# RoboBoard.net
KiCad netlist of a schematic drawn in EAGLE
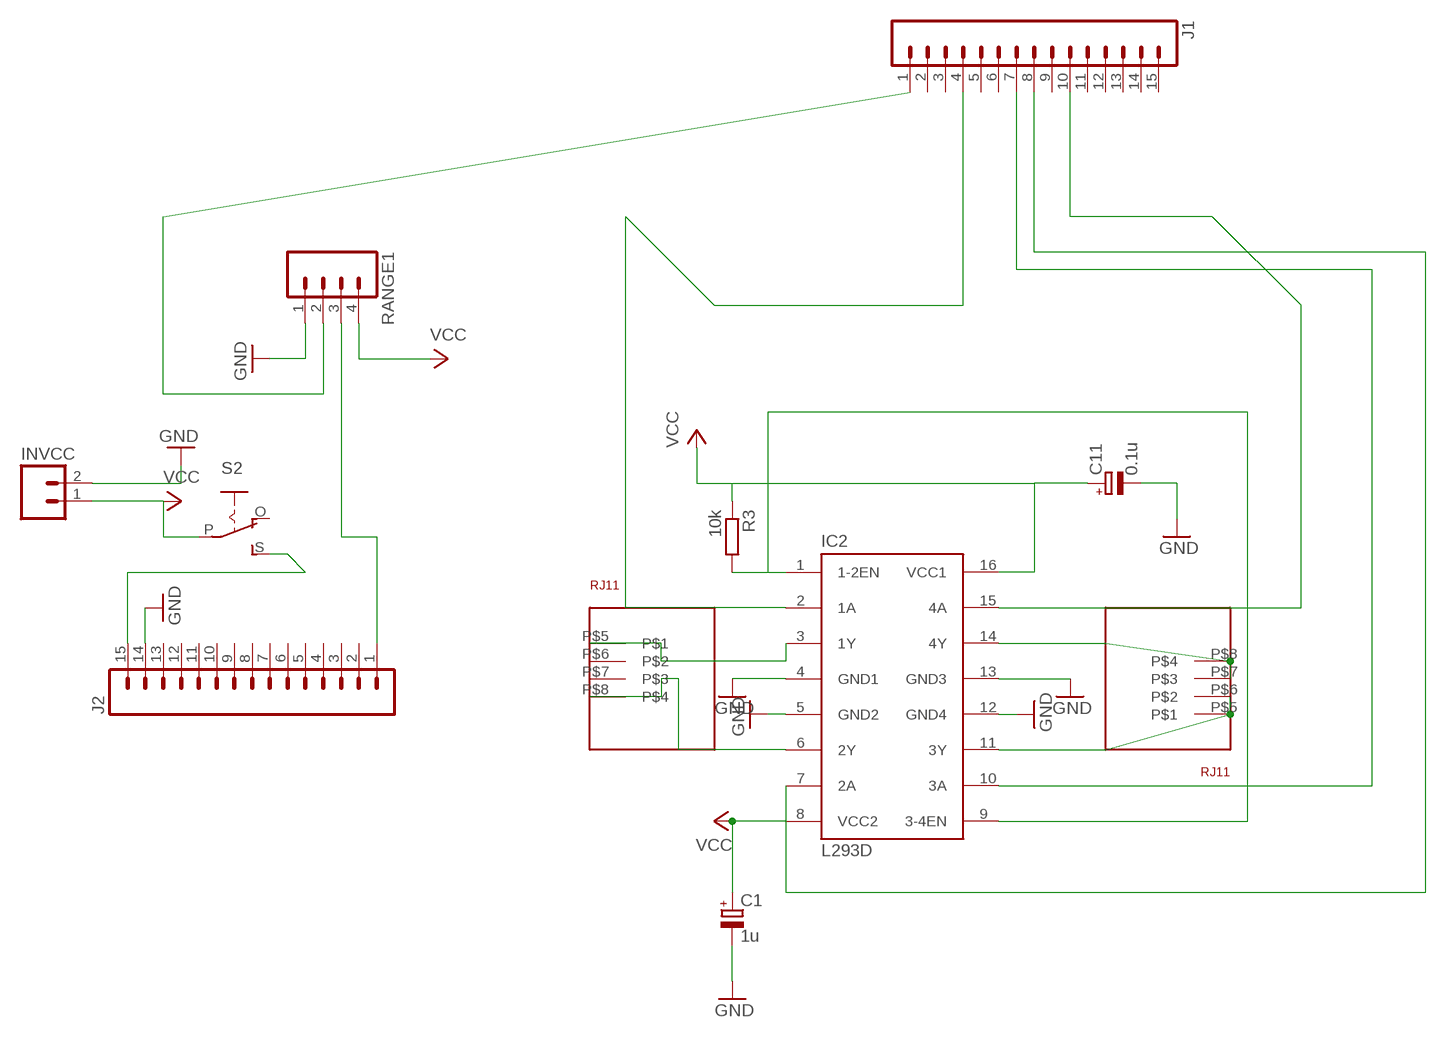
[diagram p0: schematic, sheet 1]

(export (version "E")
  (design (tool "Eeschema 10.0.6"))
  (components
    (comp (ref "C1")
      (value "1u")
      (footprint "eagle-import:E1,8-4")
      (libsource (lib "eagle-import") (part "CPOL-EUE1.8-4"))
    )
    (comp (ref "C11")
      (value "0.1u")
      (footprint "eagle-import:E1,8-4")
      (libsource (lib "eagle-import") (part "CPOL-EUE1.8-4"))
    )
    (comp (ref "IC2")
      (value "L293D")
      (footprint "eagle-import:DIL16")
      (libsource (lib "eagle-import") (part "L293D"))
    )
    (comp (ref "INVCC")
      (value "M02LOCK_LONGPADS")
      (footprint "eagle-import:1X02_LOCK_LONGPADS")
      (libsource (lib "eagle-import") (part "M02LOCK_LONGPADS"))
    )
    (comp (ref "J1")
      (value "M15LOCK_LONGPADS")
      (footprint "eagle-import:1X15_LOCK_LONGPADS")
      (libsource (lib "eagle-import") (part "M15LOCK_LONGPADS"))
    )
    (comp (ref "J2")
      (value "M15LOCK_LONGPADS")
      (footprint "eagle-import:1X15_LOCK_LONGPADS")
      (libsource (lib "eagle-import") (part "M15LOCK_LONGPADS"))
    )
    (comp (ref "R3")
      (value "10k")
      (footprint "eagle-import:0204_7")
      (libsource (lib "eagle-import") (part "R-EU_0204/7"))
    )
    (comp (ref "RANGE1")
      (value "M04LONGPADS")
      (footprint "eagle-import:1X04_LONGPADS")
      (libsource (lib "eagle-import") (part "M04LONGPADS"))
    )
    (comp (ref "RJ1")
      (value "RJ11")
      (footprint "eagle-import:RJ11-4PIN")
      (libsource (lib "eagle-import") (part "RJ11"))
    )
    (comp (ref "RJ2")
      (value "RJ11")
      (footprint "eagle-import:RJ11-4PIN")
      (libsource (lib "eagle-import") (part "RJ11"))
    )
    (comp (ref "S2")
      (value "EG1218S")
      (footprint "eagle-import:EG1218")
      (libsource (lib "eagle-import") (part "EG1218S"))
    )
  )
  (nets
    (net (code "1") (name "GND") (class "Default")
      (node (ref "C1") (pin "-") (pinfunction "-_-") (pintype "passive"))
      (node (ref "C11") (pin "-") (pinfunction "-_-") (pintype "passive"))
      (node (ref "IC2") (pin "12") (pinfunction "GND4_12") (pintype "power_in"))
      (node (ref "IC2") (pin "13") (pinfunction "GND3_13") (pintype "power_in"))
      (node (ref "IC2") (pin "4") (pinfunction "GND1_4") (pintype "power_in"))
      (node (ref "IC2") (pin "5") (pinfunction "GND2_5") (pintype "power_in"))
      (node (ref "INVCC") (pin "2") (pinfunction "2_2") (pintype "passive"))
      (node (ref "J2") (pin "14") (pinfunction "14_14") (pintype "passive"))
      (node (ref "RANGE1") (pin "1") (pinfunction "1_1") (pintype "passive"))
    )
    (net (code "2") (name "Net-(IC2-1-2EN)") (class "Default")
      (node (ref "IC2") (pin "1") (pinfunction "1-2EN_1") (pintype "input"))
      (node (ref "IC2") (pin "9") (pinfunction "3-4EN_9") (pintype "input"))
      (node (ref "R3") (pin "2") (pinfunction "2_2") (pintype "passive"))
    )
    (net (code "3") (name "Net-(IC2-1A)") (class "Default")
      (node (ref "IC2") (pin "2") (pinfunction "1A_2") (pintype "input"))
      (node (ref "J1") (pin "4") (pinfunction "4_4") (pintype "passive"))
    )
    (net (code "4") (name "Net-(IC2-1Y)") (class "Default")
      (node (ref "IC2") (pin "3") (pinfunction "1Y_3") (pintype "output"))
      (node (ref "RJ1") (pin "P$5") (pinfunction "P$1_P$5") (pintype "bidirectional"))
    )
    (net (code "5") (name "Net-(IC2-2A)") (class "Default")
      (node (ref "IC2") (pin "7") (pinfunction "2A_7") (pintype "input"))
      (node (ref "J1") (pin "8") (pinfunction "8_8") (pintype "passive"))
    )
    (net (code "6") (name "Net-(IC2-2Y)") (class "Default")
      (node (ref "IC2") (pin "6") (pinfunction "2Y_6") (pintype "output"))
      (node (ref "RJ1") (pin "P$8") (pinfunction "P$4_P$8") (pintype "bidirectional"))
    )
    (net (code "7") (name "Net-(IC2-3A)") (class "Default")
      (node (ref "IC2") (pin "10") (pinfunction "3A_10") (pintype "input"))
      (node (ref "J1") (pin "7") (pinfunction "7_7") (pintype "passive"))
    )
    (net (code "8") (name "Net-(IC2-3Y)") (class "Default")
      (node (ref "IC2") (pin "11") (pinfunction "3Y_11") (pintype "output"))
      (node (ref "RJ2") (pin "P$5") (pinfunction "P$1_P$5") (pintype "bidirectional"))
      (node (ref "RJ2") (pin "P$6") (pinfunction "P$2_P$6") (pintype "bidirectional"))
    )
    (net (code "9") (name "Net-(IC2-4A)") (class "Default")
      (node (ref "IC2") (pin "15") (pinfunction "4A_15") (pintype "input"))
      (node (ref "J1") (pin "10") (pinfunction "10_10") (pintype "passive"))
    )
    (net (code "10") (name "Net-(IC2-4Y)") (class "Default")
      (node (ref "IC2") (pin "14") (pinfunction "4Y_14") (pintype "output"))
      (node (ref "RJ2") (pin "P$7") (pinfunction "P$3_P$7") (pintype "bidirectional"))
      (node (ref "RJ2") (pin "P$8") (pinfunction "P$4_P$8") (pintype "bidirectional"))
    )
    (net (code "11") (name "Net-(J1-Pad1)") (class "Default")
      (node (ref "J1") (pin "1") (pinfunction "1_1") (pintype "passive"))
      (node (ref "RANGE1") (pin "2") (pinfunction "2_2") (pintype "passive"))
    )
    (net (code "12") (name "Net-(J2-Pad1)") (class "Default")
      (node (ref "J2") (pin "1") (pinfunction "1_1") (pintype "passive"))
      (node (ref "RANGE1") (pin "3") (pinfunction "3_3") (pintype "passive"))
    )
    (net (code "13") (name "Net-(J2-Pad15)") (class "Default")
      (node (ref "J2") (pin "15") (pinfunction "15_15") (pintype "passive"))
      (node (ref "S2") (pin "S") (pinfunction "S_S") (pintype "passive"))
    )
    (net (code "14") (name "VCC") (class "Default")
      (node (ref "C1") (pin "+") (pinfunction "+_+") (pintype "passive"))
      (node (ref "C11") (pin "+") (pinfunction "+_+") (pintype "passive"))
      (node (ref "IC2") (pin "16") (pinfunction "VCC1_16") (pintype "power_in"))
      (node (ref "IC2") (pin "8") (pinfunction "VCC2_8") (pintype "power_in"))
      (node (ref "INVCC") (pin "1") (pinfunction "1_1") (pintype "passive"))
      (node (ref "R3") (pin "1") (pinfunction "1_1") (pintype "passive"))
      (node (ref "RANGE1") (pin "4") (pinfunction "4_4") (pintype "passive"))
      (node (ref "S2") (pin "P") (pinfunction "P_P") (pintype "passive"))
    )
    (net (code "15") (name "unconnected-(J1-Pad2)") (class "Default")
      (node (ref "J1") (pin "2") (pinfunction "2_2") (pintype "passive"))
    )
    (net (code "16") (name "unconnected-(J1-Pad3)") (class "Default")
      (node (ref "J1") (pin "3") (pinfunction "3_3") (pintype "passive"))
    )
    (net (code "17") (name "unconnected-(J1-Pad5)") (class "Default")
      (node (ref "J1") (pin "5") (pinfunction "5_5") (pintype "passive"))
    )
    (net (code "18") (name "unconnected-(J1-Pad6)") (class "Default")
      (node (ref "J1") (pin "6") (pinfunction "6_6") (pintype "passive"))
    )
    (net (code "19") (name "unconnected-(J1-Pad9)") (class "Default")
      (node (ref "J1") (pin "9") (pinfunction "9_9") (pintype "passive"))
    )
    (net (code "20") (name "unconnected-(J1-Pad11)") (class "Default")
      (node (ref "J1") (pin "11") (pinfunction "11_11") (pintype "passive"))
    )
    (net (code "21") (name "unconnected-(J1-Pad12)") (class "Default")
      (node (ref "J1") (pin "12") (pinfunction "12_12") (pintype "passive"))
    )
    (net (code "22") (name "unconnected-(J1-Pad13)") (class "Default")
      (node (ref "J1") (pin "13") (pinfunction "13_13") (pintype "passive"))
    )
    (net (code "23") (name "unconnected-(J1-Pad14)") (class "Default")
      (node (ref "J1") (pin "14") (pinfunction "14_14") (pintype "passive"))
    )
    (net (code "24") (name "unconnected-(J1-Pad15)") (class "Default")
      (node (ref "J1") (pin "15") (pinfunction "15_15") (pintype "passive"))
    )
    (net (code "25") (name "unconnected-(J2-Pad2)") (class "Default")
      (node (ref "J2") (pin "2") (pinfunction "2_2") (pintype "passive"))
    )
    (net (code "26") (name "unconnected-(J2-Pad3)") (class "Default")
      (node (ref "J2") (pin "3") (pinfunction "3_3") (pintype "passive"))
    )
    (net (code "27") (name "unconnected-(J2-Pad4)") (class "Default")
      (node (ref "J2") (pin "4") (pinfunction "4_4") (pintype "passive"))
    )
    (net (code "28") (name "unconnected-(J2-Pad5)") (class "Default")
      (node (ref "J2") (pin "5") (pinfunction "5_5") (pintype "passive"))
    )
    (net (code "29") (name "unconnected-(J2-Pad6)") (class "Default")
      (node (ref "J2") (pin "6") (pinfunction "6_6") (pintype "passive"))
    )
    (net (code "30") (name "unconnected-(J2-Pad7)") (class "Default")
      (node (ref "J2") (pin "7") (pinfunction "7_7") (pintype "passive"))
    )
    (net (code "31") (name "unconnected-(J2-Pad8)") (class "Default")
      (node (ref "J2") (pin "8") (pinfunction "8_8") (pintype "passive"))
    )
    (net (code "32") (name "unconnected-(J2-Pad9)") (class "Default")
      (node (ref "J2") (pin "9") (pinfunction "9_9") (pintype "passive"))
    )
    (net (code "33") (name "unconnected-(J2-Pad10)") (class "Default")
      (node (ref "J2") (pin "10") (pinfunction "10_10") (pintype "passive"))
    )
    (net (code "34") (name "unconnected-(J2-Pad11)") (class "Default")
      (node (ref "J2") (pin "11") (pinfunction "11_11") (pintype "passive"))
    )
    (net (code "35") (name "unconnected-(J2-Pad12)") (class "Default")
      (node (ref "J2") (pin "12") (pinfunction "12_12") (pintype "passive"))
    )
    (net (code "36") (name "unconnected-(J2-Pad13)") (class "Default")
      (node (ref "J2") (pin "13") (pinfunction "13_13") (pintype "passive"))
    )
    (net (code "37") (name "unconnected-(RJ1-P$2-PadP$6)") (class "Default")
      (node (ref "RJ1") (pin "P$6") (pinfunction "P$2_P$6") (pintype "bidirectional"))
    )
    (net (code "38") (name "unconnected-(RJ1-P$3-PadP$7)") (class "Default")
      (node (ref "RJ1") (pin "P$7") (pinfunction "P$3_P$7") (pintype "bidirectional"))
    )
    (net (code "39") (name "unconnected-(S2-PadO)") (class "Default")
      (node (ref "S2") (pin "O") (pinfunction "O_O") (pintype "passive"))
    )
  )
)
